# CoreBoard2.net
KiCad netlist of a schematic drawn in Altium Designer
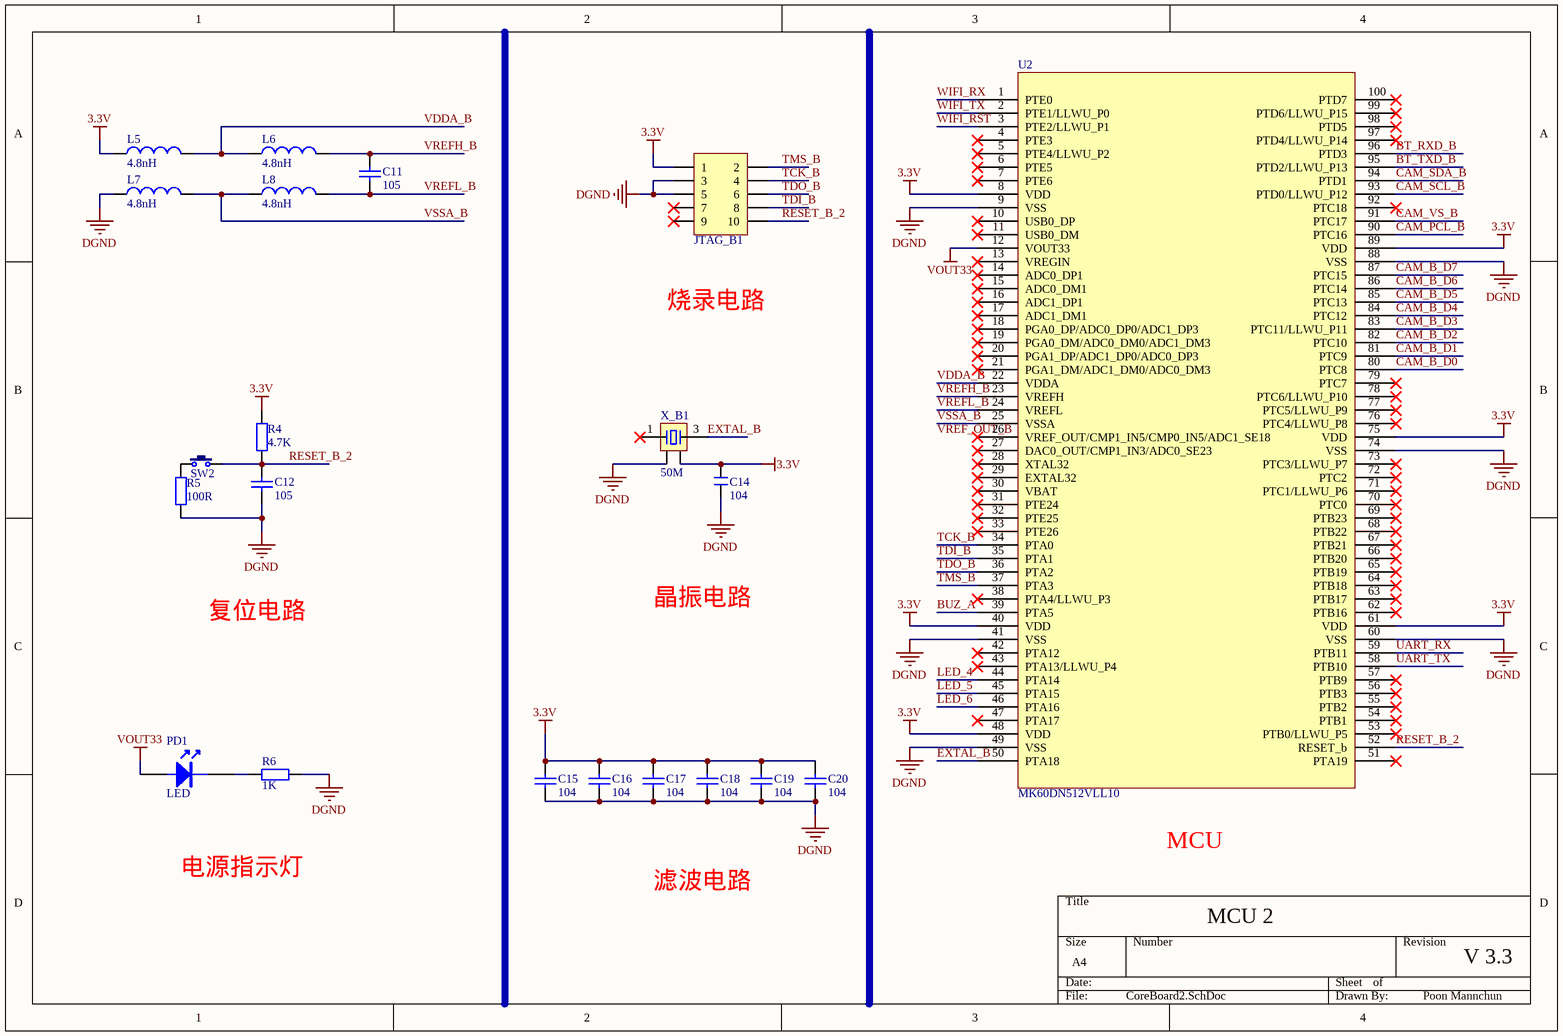
[diagram p0: CoreBoard2.SchDoc]

(export (version "E")
  (design (tool "Eeschema 10.0.6"))
  (components
    (comp (ref "C11")
      (value "105")
      (footprint "C 0805_L")
      (description "Capacitor")
      (fields (field (name "PUBLISHER") "Altium Limited"))
      (libsource (lib "6-MK60DN512VLL10核心板") (part "CAP"))
    )
    (comp (ref "C12")
      (value "105")
      (footprint "C 0805_L")
      (description "Capacitor")
      (fields (field (name "PUBLISHER") "Altium Limited"))
      (libsource (lib "6-MK60DN512VLL10核心板") (part "CAP"))
    )
    (comp (ref "C14")
      (value "104")
      (footprint "C 0805")
      (description "无极性贴片电容")
      (fields (field (name "版权归属") "源创客"))
      (libsource (lib "电阻-电容-电感") (part "C"))
    )
    (comp (ref "C15")
      (value "104")
      (footprint "C 0805_L")
      (description "Capacitor")
      (fields (field (name "PUBLISHER") "Altium Limited"))
      (libsource (lib "6-MK60DN512VLL10核心板") (part "CAP"))
    )
    (comp (ref "C16")
      (value "104")
      (footprint "C 0805_L")
      (description "Capacitor")
      (fields (field (name "PUBLISHER") "Altium Limited"))
      (libsource (lib "6-MK60DN512VLL10核心板") (part "CAP"))
    )
    (comp (ref "C17")
      (value "104")
      (footprint "C 0805_L")
      (description "Capacitor")
      (fields (field (name "PUBLISHER") "Altium Limited"))
      (libsource (lib "6-MK60DN512VLL10核心板") (part "CAP"))
    )
    (comp (ref "C18")
      (value "104")
      (footprint "C 0805_L")
      (description "Capacitor")
      (fields (field (name "PUBLISHER") "Altium Limited"))
      (libsource (lib "6-MK60DN512VLL10核心板") (part "CAP"))
    )
    (comp (ref "C19")
      (value "104")
      (footprint "C 0805_L")
      (description "Capacitor")
      (fields (field (name "PUBLISHER") "Altium Limited"))
      (libsource (lib "6-MK60DN512VLL10核心板") (part "CAP"))
    )
    (comp (ref "C20")
      (value "104")
      (footprint "C 0805_L")
      (description "Capacitor")
      (fields (field (name "PUBLISHER") "Altium Limited"))
      (libsource (lib "6-MK60DN512VLL10核心板") (part "CAP"))
    )
    (comp (ref "JTAG_B1")
      (value "Header 5X2")
      (footprint "HDR-5X2")
      (description "5*2P接插件")
      (fields (field (name "版权归属") "源创客"))
      (libsource (lib "接插件") (part "Header 5X2"))
    )
    (comp (ref "L5")
      (value "4.8nH")
      (footprint "L 0805")
      (description "Inductor")
      (fields (field (name "PUBLISHER") "Altium Limited"))
      (libsource (lib "6-MK60DN512VLL10核心板") (part "Inductor"))
    )
    (comp (ref "L6")
      (value "4.8nH")
      (footprint "L 0805")
      (description "Inductor")
      (fields (field (name "PUBLISHER") "Altium Limited"))
      (libsource (lib "6-MK60DN512VLL10核心板") (part "Inductor"))
    )
    (comp (ref "L7")
      (value "4.8nH")
      (footprint "L 0805")
      (description "Inductor")
      (fields (field (name "PUBLISHER") "Altium Limited"))
      (libsource (lib "6-MK60DN512VLL10核心板") (part "Inductor"))
    )
    (comp (ref "L8")
      (value "4.8nH")
      (footprint "L 0805")
      (description "Inductor")
      (fields (field (name "PUBLISHER") "Altium Limited"))
      (libsource (lib "6-MK60DN512VLL10核心板") (part "Inductor"))
    )
    (comp (ref "PD1")
      (value "LED")
      (footprint "LED 0805R")
      (libsource (lib "6-MK60DN512VLL10核心板") (part "LED"))
    )
    (comp (ref "R4")
      (value "4.7K")
      (footprint "R 0805_L")
      (description "Resistor")
      (fields (field (name "PUBLISHER") "Altium Limited"))
      (libsource (lib "6-MK60DN512VLL10核心板") (part "Res2"))
    )
    (comp (ref "R5")
      (value "100R")
      (footprint "R 0805_L")
      (description "Resistor")
      (fields (field (name "PUBLISHER") "Altium Limited"))
      (libsource (lib "6-MK60DN512VLL10核心板") (part "Res2"))
    )
    (comp (ref "R6")
      (value "1K")
      (footprint "R 0805_L")
      (description "Resistor")
      (fields (field (name "PUBLISHER") "Altium Limited"))
      (libsource (lib "") (part "Res2_1"))
    )
    (comp (ref "SW2")
      (value "3x6x5")
      (footprint "TSW SMD-3*6*2.5")
      (description "3x6轻触开关")
      (fields (field (name "版权归属") "源创客"))
      (libsource (lib "按键-开关") (part "TSW 3x6"))
    )
    (comp (ref "U2")
      (value "MK60DN512VLL10")
      (footprint "LQFP100 14x14_N")
      (description "MK60DN512ZVLL10")
      (libsource (lib "6-MK60DN512VLL10核心板") (part "MK60DN512ZVLQ10"))
    )
    (comp (ref "X_B1")
      (value "50M")
      (footprint "OSC 5032-4P")
      (description "4脚晶振")
      (fields (field (name "版权归属") "源创客"))
      (libsource (lib "保险丝-晶振") (part "XTAL-4"))
    )
  )
  (nets
    (net (code "1") (name "/BT_RXD_B") (class "Default")
      (node (ref "U2") (pin "96") (pinfunction "PTD3_96") (pintype "passive"))
    )
    (net (code "2") (name "/BT_TXD_B") (class "Default")
      (node (ref "U2") (pin "95") (pinfunction "PTD2/LLWU_P13_95") (pintype "passive"))
    )
    (net (code "3") (name "/BUZ_A") (class "Default")
      (node (ref "U2") (pin "39") (pinfunction "PTA5_39") (pintype "passive"))
    )
    (net (code "4") (name "/CAM_B_D0") (class "Default")
      (node (ref "U2") (pin "80") (pinfunction "PTC8_80") (pintype "passive"))
    )
    (net (code "5") (name "/CAM_B_D1") (class "Default")
      (node (ref "U2") (pin "81") (pinfunction "PTC9_81") (pintype "passive"))
    )
    (net (code "6") (name "/CAM_B_D2") (class "Default")
      (node (ref "U2") (pin "82") (pinfunction "PTC10_82") (pintype "passive"))
    )
    (net (code "7") (name "/CAM_B_D3") (class "Default")
      (node (ref "U2") (pin "83") (pinfunction "PTC11/LLWU_P11_83") (pintype "passive"))
    )
    (net (code "8") (name "/CAM_B_D4") (class "Default")
      (node (ref "U2") (pin "84") (pinfunction "PTC12_84") (pintype "passive"))
    )
    (net (code "9") (name "/CAM_B_D5") (class "Default")
      (node (ref "U2") (pin "85") (pinfunction "PTC13_85") (pintype "passive"))
    )
    (net (code "10") (name "/CAM_B_D6") (class "Default")
      (node (ref "U2") (pin "86") (pinfunction "PTC14_86") (pintype "passive"))
    )
    (net (code "11") (name "/CAM_B_D7") (class "Default")
      (node (ref "U2") (pin "87") (pinfunction "PTC15_87") (pintype "passive"))
    )
    (net (code "12") (name "/CAM_PCL_B") (class "Default")
      (node (ref "U2") (pin "90") (pinfunction "PTC16_90") (pintype "passive"))
    )
    (net (code "13") (name "/CAM_SCL_B") (class "Default")
      (node (ref "U2") (pin "93") (pinfunction "PTD0/LLWU_P12_93") (pintype "passive"))
    )
    (net (code "14") (name "/CAM_SDA_B") (class "Default")
      (node (ref "U2") (pin "94") (pinfunction "PTD1_94") (pintype "passive"))
    )
    (net (code "15") (name "/CAM_VS_B") (class "Default")
      (node (ref "U2") (pin "91") (pinfunction "PTC17_91") (pintype "passive"))
    )
    (net (code "16") (name "/EXTAL_B") (class "Default")
      (node (ref "U2") (pin "50") (pinfunction "PTA18_50") (pintype "passive"))
      (node (ref "X_B1") (pin "3") (pinfunction "3_3") (pintype "passive"))
    )
    (net (code "17") (name "/LED_4") (class "Default")
      (node (ref "U2") (pin "44") (pinfunction "PTA14_44") (pintype "passive"))
    )
    (net (code "18") (name "/LED_5") (class "Default")
      (node (ref "U2") (pin "45") (pinfunction "PTA15_45") (pintype "passive"))
    )
    (net (code "19") (name "/LED_6") (class "Default")
      (node (ref "U2") (pin "46") (pinfunction "PTA16_46") (pintype "passive"))
    )
    (net (code "20") (name "/RESET_B_2") (class "Default")
      (node (ref "C12") (pin "2") (pinfunction "2_2") (pintype "passive"))
      (node (ref "JTAG_B1") (pin "10") (pinfunction "10_10") (pintype "passive"))
      (node (ref "R4") (pin "1") (pinfunction "1_1") (pintype "passive"))
      (node (ref "SW2") (pin "2") (pinfunction "2_2") (pintype "passive"))
      (node (ref "U2") (pin "52") (pinfunction "RESET_b_52") (pintype "passive"))
    )
    (net (code "21") (name "/TCK_B") (class "Default")
      (node (ref "JTAG_B1") (pin "4") (pinfunction "4_4") (pintype "passive"))
      (node (ref "U2") (pin "34") (pinfunction "PTA0_34") (pintype "passive"))
    )
    (net (code "22") (name "/TDI_B") (class "Default")
      (node (ref "JTAG_B1") (pin "8") (pinfunction "8_8") (pintype "passive"))
      (node (ref "U2") (pin "35") (pinfunction "PTA1_35") (pintype "passive"))
    )
    (net (code "23") (name "/TDO_B") (class "Default")
      (node (ref "JTAG_B1") (pin "6") (pinfunction "6_6") (pintype "passive"))
      (node (ref "U2") (pin "36") (pinfunction "PTA2_36") (pintype "passive"))
    )
    (net (code "24") (name "/TMS_B") (class "Default")
      (node (ref "JTAG_B1") (pin "2") (pinfunction "2_2") (pintype "passive"))
      (node (ref "U2") (pin "37") (pinfunction "PTA3_37") (pintype "passive"))
    )
    (net (code "25") (name "/UART_RX") (class "Default")
      (node (ref "U2") (pin "59") (pinfunction "PTB11_59") (pintype "passive"))
    )
    (net (code "26") (name "/UART_TX") (class "Default")
      (node (ref "U2") (pin "58") (pinfunction "PTB10_58") (pintype "passive"))
    )
    (net (code "27") (name "/VDDA_B") (class "Default")
      (node (ref "L5") (pin "2") (pinfunction "2_2") (pintype "passive"))
      (node (ref "L6") (pin "1") (pinfunction "1_1") (pintype "passive"))
      (node (ref "U2") (pin "22") (pinfunction "VDDA_22") (pintype "passive"))
    )
    (net (code "28") (name "/VREFH_B") (class "Default")
      (node (ref "C11") (pin "2") (pinfunction "2_2") (pintype "passive"))
      (node (ref "L6") (pin "2") (pinfunction "2_2") (pintype "passive"))
      (node (ref "U2") (pin "23") (pinfunction "VREFH_23") (pintype "passive"))
    )
    (net (code "29") (name "/VREFL_B") (class "Default")
      (node (ref "C11") (pin "1") (pinfunction "1_1") (pintype "passive"))
      (node (ref "L8") (pin "2") (pinfunction "2_2") (pintype "passive"))
      (node (ref "U2") (pin "24") (pinfunction "VREFL_24") (pintype "passive"))
    )
    (net (code "31") (name "/VSSA_B") (class "Default")
      (node (ref "L7") (pin "2") (pinfunction "2_2") (pintype "passive"))
      (node (ref "L8") (pin "1") (pinfunction "1_1") (pintype "passive"))
      (node (ref "U2") (pin "25") (pinfunction "VSSA_25") (pintype "passive"))
    )
    (net (code "32") (name "/WIFI_RST") (class "Default")
      (node (ref "U2") (pin "3") (pinfunction "PTE2/LLWU_P1_3") (pintype "passive"))
    )
    (net (code "33") (name "/WIFI_RX") (class "Default")
      (node (ref "U2") (pin "1") (pinfunction "PTE0_1") (pintype "passive"))
    )
    (net (code "34") (name "/WIFI_TX") (class "Default")
      (node (ref "U2") (pin "2") (pinfunction "PTE1/LLWU_P0_2") (pintype "passive"))
    )
    (net (code "35") (name "3.3V") (class "Default")
      (node (ref "C14") (pin "2") (pinfunction "2_2") (pintype "passive"))
      (node (ref "C15") (pin "2") (pinfunction "2_2") (pintype "passive"))
      (node (ref "C16") (pin "2") (pinfunction "2_2") (pintype "passive"))
      (node (ref "C17") (pin "2") (pinfunction "2_2") (pintype "passive"))
      (node (ref "C18") (pin "2") (pinfunction "2_2") (pintype "passive"))
      (node (ref "C19") (pin "2") (pinfunction "2_2") (pintype "passive"))
      (node (ref "C20") (pin "2") (pinfunction "2_2") (pintype "passive"))
      (node (ref "JTAG_B1") (pin "1") (pinfunction "1_1") (pintype "passive"))
      (node (ref "L5") (pin "1") (pinfunction "1_1") (pintype "passive"))
      (node (ref "R4") (pin "2") (pinfunction "2_2") (pintype "passive"))
      (node (ref "U2") (pin "40") (pinfunction "VDD_40") (pintype "passive"))
      (node (ref "U2") (pin "48") (pinfunction "VDD_48") (pintype "passive"))
      (node (ref "U2") (pin "61") (pinfunction "VDD_61") (pintype "passive"))
      (node (ref "U2") (pin "75") (pinfunction "VDD_75") (pintype "passive"))
      (node (ref "U2") (pin "8") (pinfunction "VDD_8") (pintype "passive"))
      (node (ref "U2") (pin "89") (pinfunction "VDD_89") (pintype "passive"))
      (node (ref "X_B1") (pin "4") (pinfunction "4_4") (pintype "passive"))
    )
    (net (code "36") (name "DGND") (class "Default")
      (node (ref "C12") (pin "1") (pinfunction "1_1") (pintype "passive"))
      (node (ref "C14") (pin "1") (pinfunction "1_1") (pintype "passive"))
      (node (ref "C15") (pin "1") (pinfunction "1_1") (pintype "passive"))
      (node (ref "C16") (pin "1") (pinfunction "1_1") (pintype "passive"))
      (node (ref "C17") (pin "1") (pinfunction "1_1") (pintype "passive"))
      (node (ref "C18") (pin "1") (pinfunction "1_1") (pintype "passive"))
      (node (ref "C19") (pin "1") (pinfunction "1_1") (pintype "passive"))
      (node (ref "C20") (pin "1") (pinfunction "1_1") (pintype "passive"))
      (node (ref "JTAG_B1") (pin "3") (pinfunction "3_3") (pintype "passive"))
      (node (ref "JTAG_B1") (pin "5") (pinfunction "5_5") (pintype "passive"))
      (node (ref "L7") (pin "1") (pinfunction "1_1") (pintype "passive"))
      (node (ref "R5") (pin "1") (pinfunction "1_1") (pintype "passive"))
      (node (ref "R6") (pin "2") (pinfunction "2_2") (pintype "passive"))
      (node (ref "U2") (pin "41") (pinfunction "VSS_41") (pintype "passive"))
      (node (ref "U2") (pin "49") (pinfunction "VSS_49") (pintype "passive"))
      (node (ref "U2") (pin "60") (pinfunction "VSS_60") (pintype "passive"))
      (node (ref "U2") (pin "74") (pinfunction "VSS_74") (pintype "passive"))
      (node (ref "U2") (pin "88") (pinfunction "VSS_88") (pintype "passive"))
      (node (ref "U2") (pin "9") (pinfunction "VSS_9") (pintype "passive"))
      (node (ref "X_B1") (pin "2") (pinfunction "2_2") (pintype "passive"))
    )
    (net (code "37") (name "Net-(PD1-2)") (class "Default")
      (node (ref "PD1") (pin "K") (pinfunction "2_K") (pintype "passive"))
      (node (ref "R6") (pin "1") (pinfunction "1_1") (pintype "passive"))
    )
    (net (code "38") (name "Net-(R5-Pad2)") (class "Default")
      (node (ref "R5") (pin "2") (pinfunction "2_2") (pintype "passive"))
      (node (ref "SW2") (pin "1") (pinfunction "1_1") (pintype "passive"))
    )
    (net (code "39") (name "VOUT33") (class "Default")
      (node (ref "PD1") (pin "A") (pinfunction "1_A") (pintype "passive"))
      (node (ref "U2") (pin "12") (pinfunction "VOUT33_12") (pintype "passive"))
    )
    (net (code "40") (name "unconnected-(JTAG_B1-Pad7)") (class "Default")
      (node (ref "JTAG_B1") (pin "7") (pinfunction "7_7") (pintype "passive+no_connect"))
    )
    (net (code "41") (name "unconnected-(JTAG_B1-Pad9)") (class "Default")
      (node (ref "JTAG_B1") (pin "9") (pinfunction "9_9") (pintype "passive+no_connect"))
    )
    (net (code "42") (name "unconnected-(U2-ADC0_DM1-Pad15)") (class "Default")
      (node (ref "U2") (pin "15") (pinfunction "ADC0_DM1_15") (pintype "passive+no_connect"))
    )
    (net (code "43") (name "unconnected-(U2-ADC0_DP1-Pad14)") (class "Default")
      (node (ref "U2") (pin "14") (pinfunction "ADC0_DP1_14") (pintype "passive+no_connect"))
    )
    (net (code "44") (name "unconnected-(U2-ADC1_DM1-Pad17)") (class "Default")
      (node (ref "U2") (pin "17") (pinfunction "ADC1_DM1_17") (pintype "passive+no_connect"))
    )
    (net (code "45") (name "unconnected-(U2-ADC1_DP1-Pad16)") (class "Default")
      (node (ref "U2") (pin "16") (pinfunction "ADC1_DP1_16") (pintype "passive+no_connect"))
    )
    (net (code "46") (name "unconnected-(U2-DAC0_OUT{slash}CMP1_IN3{slash}ADC0_SE23-Pad27)") (class "Default")
      (node (ref "U2") (pin "27") (pinfunction "DAC0_OUT/CMP1_IN3/ADC0_SE23_27") (pintype "passive+no_connect"))
    )
    (net (code "47") (name "unconnected-(U2-EXTAL32-Pad29)") (class "Default")
      (node (ref "U2") (pin "29") (pinfunction "EXTAL32_29") (pintype "passive+no_connect"))
    )
    (net (code "48") (name "unconnected-(U2-PGA0_DM{slash}ADC0_DM0{slash}ADC1_DM3-Pad19)") (class "Default")
      (node (ref "U2") (pin "19") (pinfunction "PGA0_DM/ADC0_DM0/ADC1_DM3_19") (pintype "passive+no_connect"))
    )
    (net (code "49") (name "unconnected-(U2-PGA0_DP{slash}ADC0_DP0{slash}ADC1_DP3-Pad18)") (class "Default")
      (node (ref "U2") (pin "18") (pinfunction "PGA0_DP/ADC0_DP0/ADC1_DP3_18") (pintype "passive+no_connect"))
    )
    (net (code "50") (name "unconnected-(U2-PGA1_DM{slash}ADC1_DM0{slash}ADC0_DM3-Pad21)") (class "Default")
      (node (ref "U2") (pin "21") (pinfunction "PGA1_DM/ADC1_DM0/ADC0_DM3_21") (pintype "passive+no_connect"))
    )
    (net (code "51") (name "unconnected-(U2-PGA1_DP{slash}ADC1_DP0{slash}ADC0_DP3-Pad20)") (class "Default")
      (node (ref "U2") (pin "20") (pinfunction "PGA1_DP/ADC1_DP0/ADC0_DP3_20") (pintype "passive+no_connect"))
    )
    (net (code "52") (name "unconnected-(U2-PTA4{slash}LLWU_P3-Pad38)") (class "Default")
      (node (ref "U2") (pin "38") (pinfunction "PTA4/LLWU_P3_38") (pintype "passive+no_connect"))
    )
    (net (code "53") (name "unconnected-(U2-PTA12-Pad42)") (class "Default")
      (node (ref "U2") (pin "42") (pinfunction "PTA12_42") (pintype "passive+no_connect"))
    )
    (net (code "54") (name "unconnected-(U2-PTA13{slash}LLWU_P4-Pad43)") (class "Default")
      (node (ref "U2") (pin "43") (pinfunction "PTA13/LLWU_P4_43") (pintype "passive+no_connect"))
    )
    (net (code "55") (name "unconnected-(U2-PTA17-Pad47)") (class "Default")
      (node (ref "U2") (pin "47") (pinfunction "PTA17_47") (pintype "passive+no_connect"))
    )
    (net (code "56") (name "unconnected-(U2-PTA19-Pad51)") (class "Default")
      (node (ref "U2") (pin "51") (pinfunction "PTA19_51") (pintype "passive+no_connect"))
    )
    (net (code "57") (name "unconnected-(U2-PTB0{slash}LLWU_P5-Pad53)") (class "Default")
      (node (ref "U2") (pin "53") (pinfunction "PTB0/LLWU_P5_53") (pintype "passive+no_connect"))
    )
    (net (code "58") (name "unconnected-(U2-PTB1-Pad54)") (class "Default")
      (node (ref "U2") (pin "54") (pinfunction "PTB1_54") (pintype "passive+no_connect"))
    )
    (net (code "59") (name "unconnected-(U2-PTB2-Pad55)") (class "Default")
      (node (ref "U2") (pin "55") (pinfunction "PTB2_55") (pintype "passive+no_connect"))
    )
    (net (code "60") (name "unconnected-(U2-PTB3-Pad56)") (class "Default")
      (node (ref "U2") (pin "56") (pinfunction "PTB3_56") (pintype "passive+no_connect"))
    )
    (net (code "61") (name "unconnected-(U2-PTB9-Pad57)") (class "Default")
      (node (ref "U2") (pin "57") (pinfunction "PTB9_57") (pintype "passive+no_connect"))
    )
    (net (code "62") (name "unconnected-(U2-PTB16-Pad62)") (class "Default")
      (node (ref "U2") (pin "62") (pinfunction "PTB16_62") (pintype "passive+no_connect"))
    )
    (net (code "63") (name "unconnected-(U2-PTB17-Pad63)") (class "Default")
      (node (ref "U2") (pin "63") (pinfunction "PTB17_63") (pintype "passive+no_connect"))
    )
    (net (code "64") (name "unconnected-(U2-PTB18-Pad64)") (class "Default")
      (node (ref "U2") (pin "64") (pinfunction "PTB18_64") (pintype "passive+no_connect"))
    )
    (net (code "65") (name "unconnected-(U2-PTB19-Pad65)") (class "Default")
      (node (ref "U2") (pin "65") (pinfunction "PTB19_65") (pintype "passive+no_connect"))
    )
    (net (code "66") (name "unconnected-(U2-PTB20-Pad66)") (class "Default")
      (node (ref "U2") (pin "66") (pinfunction "PTB20_66") (pintype "passive+no_connect"))
    )
    (net (code "67") (name "unconnected-(U2-PTB21-Pad67)") (class "Default")
      (node (ref "U2") (pin "67") (pinfunction "PTB21_67") (pintype "passive+no_connect"))
    )
    (net (code "68") (name "unconnected-(U2-PTB22-Pad68)") (class "Default")
      (node (ref "U2") (pin "68") (pinfunction "PTB22_68") (pintype "passive+no_connect"))
    )
    (net (code "69") (name "unconnected-(U2-PTB23-Pad69)") (class "Default")
      (node (ref "U2") (pin "69") (pinfunction "PTB23_69") (pintype "passive+no_connect"))
    )
    (net (code "70") (name "unconnected-(U2-PTC0-Pad70)") (class "Default")
      (node (ref "U2") (pin "70") (pinfunction "PTC0_70") (pintype "passive+no_connect"))
    )
    (net (code "71") (name "unconnected-(U2-PTC1{slash}LLWU_P6-Pad71)") (class "Default")
      (node (ref "U2") (pin "71") (pinfunction "PTC1/LLWU_P6_71") (pintype "passive+no_connect"))
    )
    (net (code "72") (name "unconnected-(U2-PTC2-Pad72)") (class "Default")
      (node (ref "U2") (pin "72") (pinfunction "PTC2_72") (pintype "passive+no_connect"))
    )
    (net (code "73") (name "unconnected-(U2-PTC3{slash}LLWU_P7-Pad73)") (class "Default")
      (node (ref "U2") (pin "73") (pinfunction "PTC3/LLWU_P7_73") (pintype "passive+no_connect"))
    )
    (net (code "74") (name "unconnected-(U2-PTC4{slash}LLWU_P8-Pad76)") (class "Default")
      (node (ref "U2") (pin "76") (pinfunction "PTC4/LLWU_P8_76") (pintype "passive+no_connect"))
    )
    (net (code "75") (name "unconnected-(U2-PTC5{slash}LLWU_P9-Pad77)") (class "Default")
      (node (ref "U2") (pin "77") (pinfunction "PTC5/LLWU_P9_77") (pintype "passive+no_connect"))
    )
    (net (code "76") (name "unconnected-(U2-PTC6{slash}LLWU_P10-Pad78)") (class "Default")
      (node (ref "U2") (pin "78") (pinfunction "PTC6/LLWU_P10_78") (pintype "passive+no_connect"))
    )
    (net (code "77") (name "unconnected-(U2-PTC7-Pad79)") (class "Default")
      (node (ref "U2") (pin "79") (pinfunction "PTC7_79") (pintype "passive+no_connect"))
    )
    (net (code "78") (name "unconnected-(U2-PTC18-Pad92)") (class "Default")
      (node (ref "U2") (pin "92") (pinfunction "PTC18_92") (pintype "passive+no_connect"))
    )
    (net (code "79") (name "unconnected-(U2-PTD4{slash}LLWU_P14-Pad97)") (class "Default")
      (node (ref "U2") (pin "97") (pinfunction "PTD4/LLWU_P14_97") (pintype "passive+no_connect"))
    )
    (net (code "80") (name "unconnected-(U2-PTD5-Pad98)") (class "Default")
      (node (ref "U2") (pin "98") (pinfunction "PTD5_98") (pintype "passive+no_connect"))
    )
    (net (code "81") (name "unconnected-(U2-PTD6{slash}LLWU_P15-Pad99)") (class "Default")
      (node (ref "U2") (pin "99") (pinfunction "PTD6/LLWU_P15_99") (pintype "passive+no_connect"))
    )
    (net (code "82") (name "unconnected-(U2-PTD7-Pad100)") (class "Default")
      (node (ref "U2") (pin "100") (pinfunction "PTD7_100") (pintype "passive+no_connect"))
    )
    (net (code "83") (name "unconnected-(U2-PTE3-Pad4)") (class "Default")
      (node (ref "U2") (pin "4") (pinfunction "PTE3_4") (pintype "passive+no_connect"))
    )
    (net (code "84") (name "unconnected-(U2-PTE4{slash}LLWU_P2-Pad5)") (class "Default")
      (node (ref "U2") (pin "5") (pinfunction "PTE4/LLWU_P2_5") (pintype "passive+no_connect"))
    )
    (net (code "85") (name "unconnected-(U2-PTE5-Pad6)") (class "Default")
      (node (ref "U2") (pin "6") (pinfunction "PTE5_6") (pintype "passive+no_connect"))
    )
    (net (code "86") (name "unconnected-(U2-PTE6-Pad7)") (class "Default")
      (node (ref "U2") (pin "7") (pinfunction "PTE6_7") (pintype "passive+no_connect"))
    )
    (net (code "87") (name "unconnected-(U2-PTE24-Pad31)") (class "Default")
      (node (ref "U2") (pin "31") (pinfunction "PTE24_31") (pintype "passive+no_connect"))
    )
    (net (code "88") (name "unconnected-(U2-PTE25-Pad32)") (class "Default")
      (node (ref "U2") (pin "32") (pinfunction "PTE25_32") (pintype "passive+no_connect"))
    )
    (net (code "89") (name "unconnected-(U2-PTE26-Pad33)") (class "Default")
      (node (ref "U2") (pin "33") (pinfunction "PTE26_33") (pintype "passive+no_connect"))
    )
    (net (code "90") (name "unconnected-(U2-USB0_DM-Pad11)") (class "Default")
      (node (ref "U2") (pin "11") (pinfunction "USB0_DM_11") (pintype "passive+no_connect"))
    )
    (net (code "91") (name "unconnected-(U2-USB0_DP-Pad10)") (class "Default")
      (node (ref "U2") (pin "10") (pinfunction "USB0_DP_10") (pintype "passive+no_connect"))
    )
    (net (code "92") (name "unconnected-(U2-VBAT-Pad30)") (class "Default")
      (node (ref "U2") (pin "30") (pinfunction "VBAT_30") (pintype "passive+no_connect"))
    )
    (net (code "93") (name "unconnected-(U2-VREF_OUT{slash}CMP1_IN5{slash}CMP0_IN5{slash}ADC1_SE18-Pad26)") (class "Default")
      (node (ref "U2") (pin "26") (pinfunction "VREF_OUT/CMP1_IN5/CMP0_IN5/ADC1_SE18_26") (pintype "passive+no_connect"))
    )
    (net (code "94") (name "unconnected-(U2-VREGIN-Pad13)") (class "Default")
      (node (ref "U2") (pin "13") (pinfunction "VREGIN_13") (pintype "passive+no_connect"))
    )
    (net (code "95") (name "unconnected-(U2-XTAL32-Pad28)") (class "Default")
      (node (ref "U2") (pin "28") (pinfunction "XTAL32_28") (pintype "passive+no_connect"))
    )
    (net (code "96") (name "unconnected-(X_B1-Pad1)") (class "Default")
      (node (ref "X_B1") (pin "1") (pinfunction "1_1") (pintype "passive+no_connect"))
    )
  )
)
